# untitled.net
KiCad netlist of a schematic drawn in EAGLE
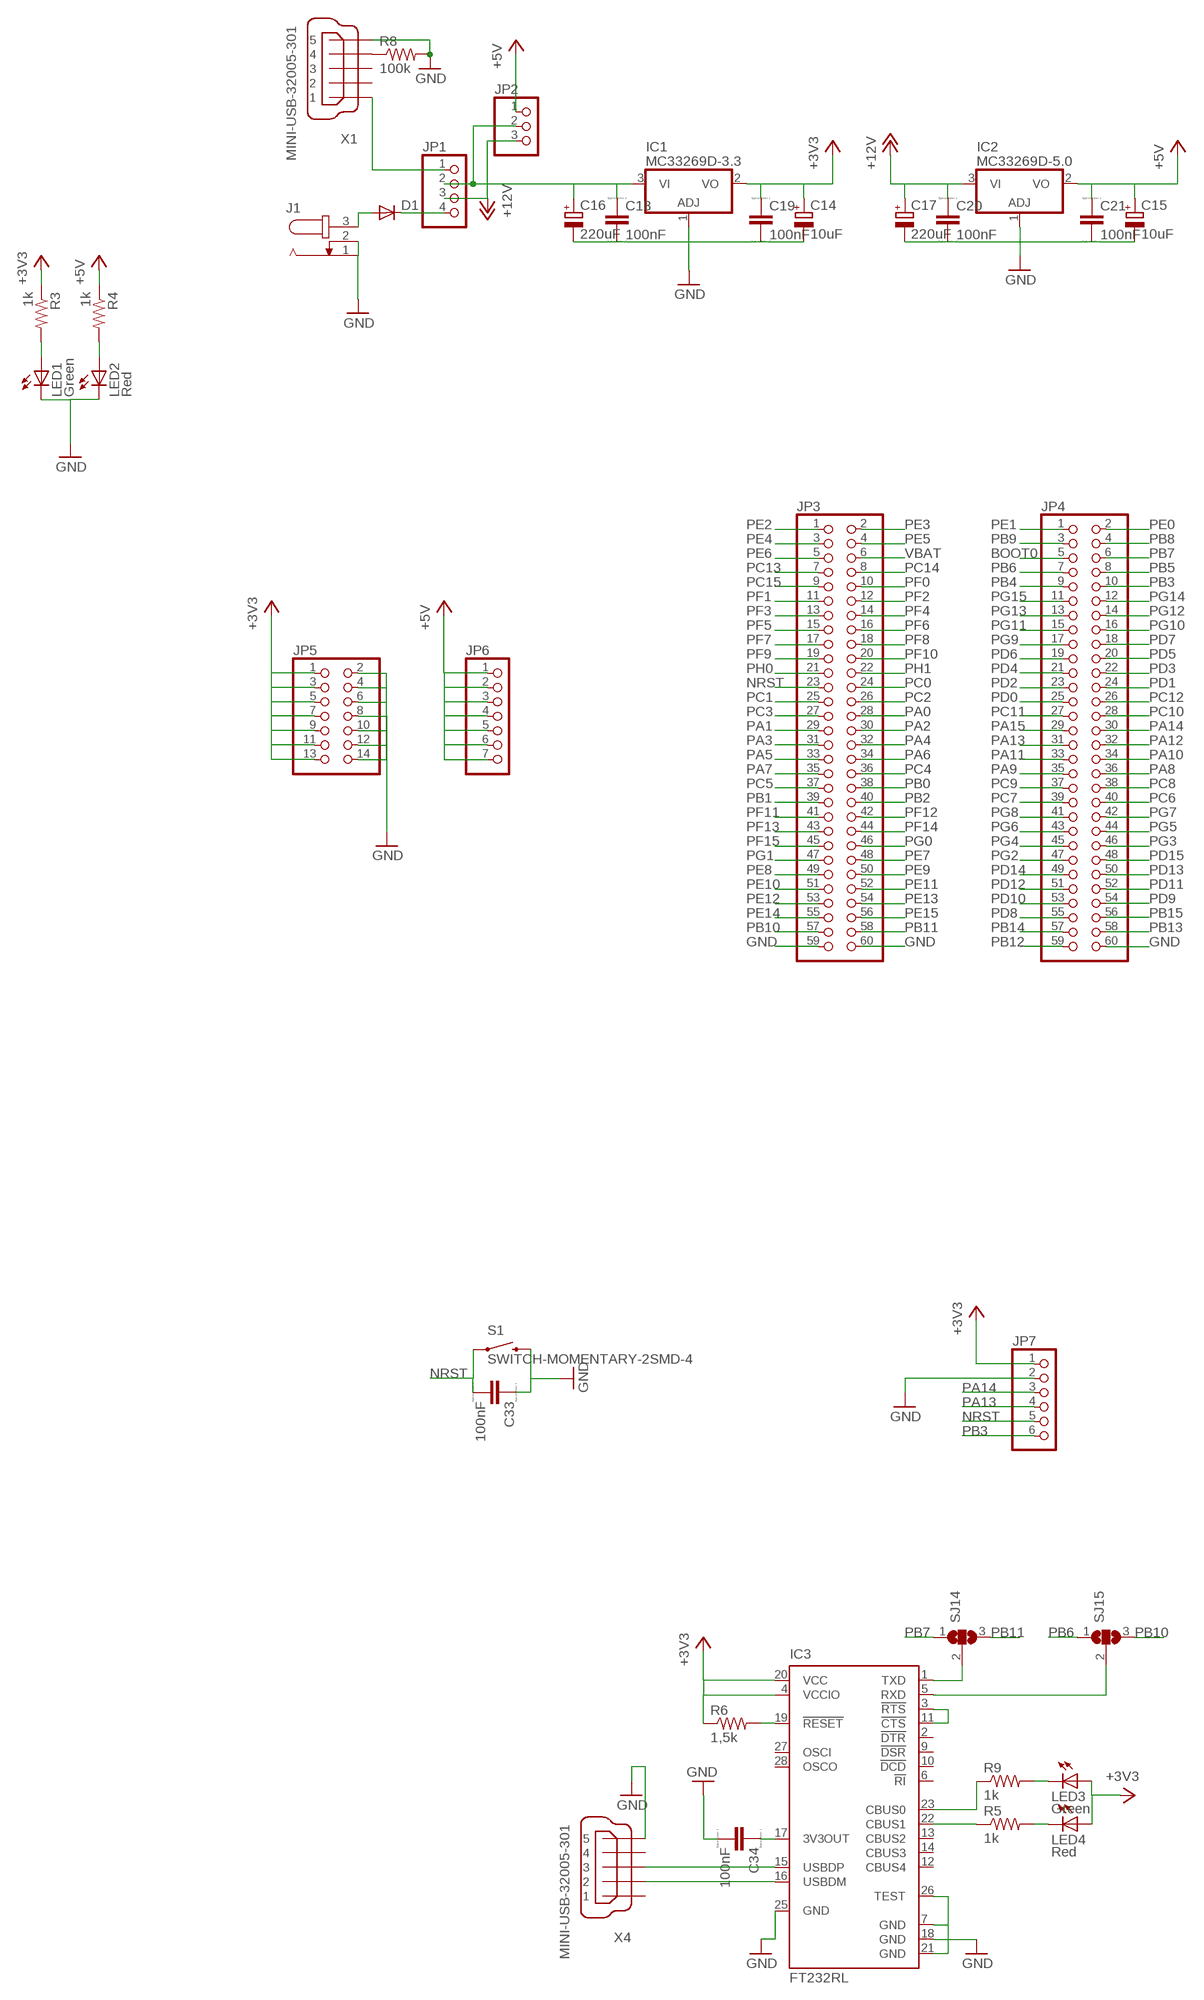
[diagram p0: schematic, sheet 1, part 1 of 2]
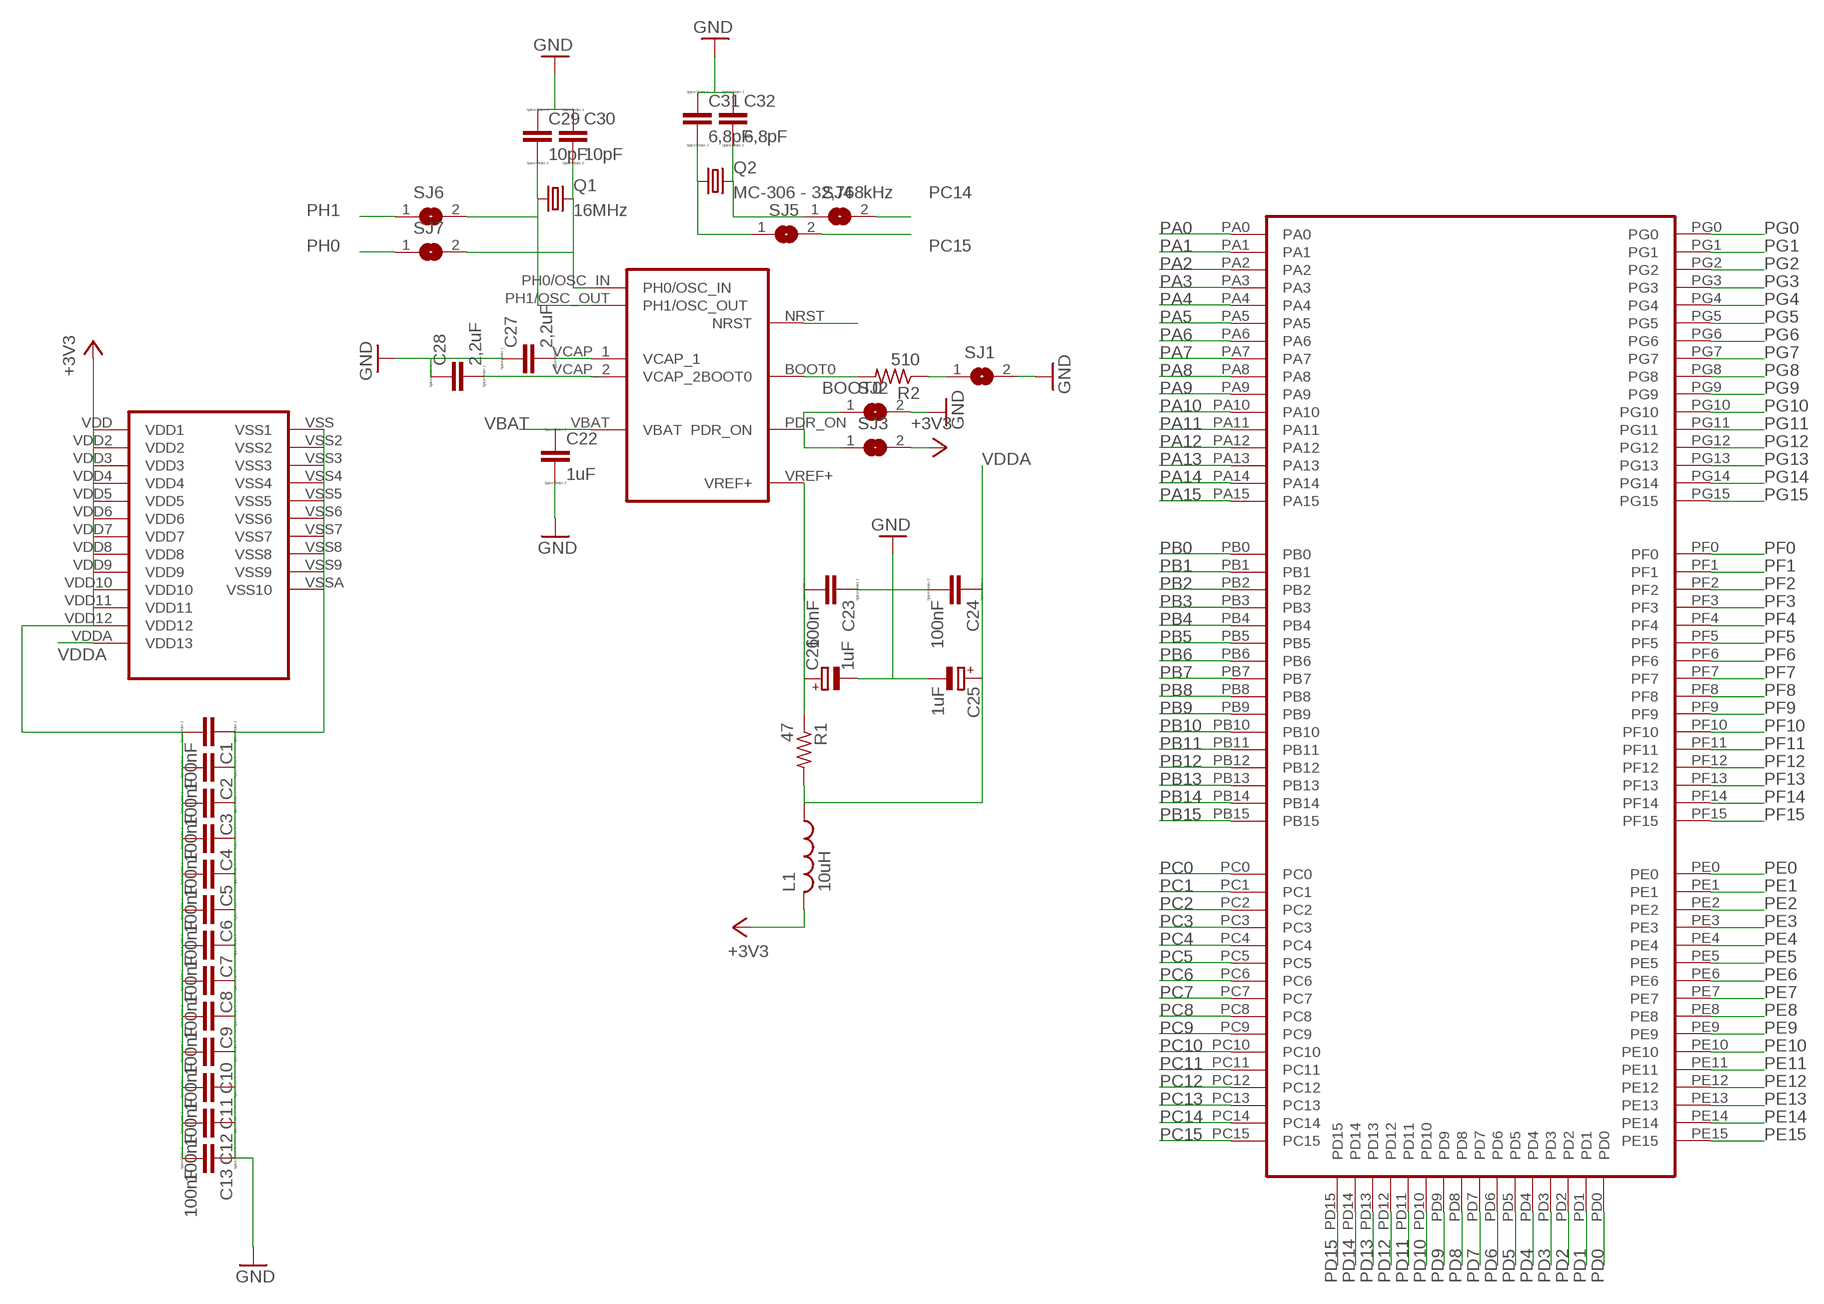
[diagram p1: schematic, sheet 1, part 2 of 2]

(export (version "E")
  (design (tool "Eeschema 10.0.6"))
  (components
    (comp (ref "C1")
      (value "100nF")
      (footprint "eagle-import:C2012")
      (libsource (lib "eagle-import") (part "CC2012"))
    )
    (comp (ref "C2")
      (value "100nF")
      (footprint "eagle-import:C2012")
      (libsource (lib "eagle-import") (part "CC2012"))
    )
    (comp (ref "C3")
      (value "100nF")
      (footprint "eagle-import:C2012")
      (libsource (lib "eagle-import") (part "CC2012"))
    )
    (comp (ref "C4")
      (value "100nF")
      (footprint "eagle-import:C2012")
      (libsource (lib "eagle-import") (part "CC2012"))
    )
    (comp (ref "C5")
      (value "100nF")
      (footprint "eagle-import:C2012")
      (libsource (lib "eagle-import") (part "CC2012"))
    )
    (comp (ref "C6")
      (value "100nF")
      (footprint "eagle-import:C2012")
      (libsource (lib "eagle-import") (part "CC2012"))
    )
    (comp (ref "C7")
      (value "100nF")
      (footprint "eagle-import:C2012")
      (libsource (lib "eagle-import") (part "CC2012"))
    )
    (comp (ref "C8")
      (value "100nF")
      (footprint "eagle-import:C2012")
      (libsource (lib "eagle-import") (part "CC2012"))
    )
    (comp (ref "C9")
      (value "100nF")
      (footprint "eagle-import:C2012")
      (libsource (lib "eagle-import") (part "CC2012"))
    )
    (comp (ref "C10")
      (value "100nF")
      (footprint "eagle-import:C2012")
      (libsource (lib "eagle-import") (part "CC2012"))
    )
    (comp (ref "C11")
      (value "100nF")
      (footprint "eagle-import:C2012")
      (libsource (lib "eagle-import") (part "CC2012"))
    )
    (comp (ref "C12")
      (value "100nF")
      (footprint "eagle-import:C2012")
      (libsource (lib "eagle-import") (part "CC2012"))
    )
    (comp (ref "C13")
      (value "100nF")
      (footprint "eagle-import:C2012")
      (libsource (lib "eagle-import") (part "CC2012"))
    )
    (comp (ref "C14")
      (value "10uF")
      (footprint "eagle-import:SMC_C")
      (libsource (lib "eagle-import") (part "resistor_CPOL-EUSMCC"))
    )
    (comp (ref "C15")
      (value "10uF")
      (footprint "eagle-import:SMC_C")
      (libsource (lib "eagle-import") (part "resistor_CPOL-EUSMCC"))
    )
    (comp (ref "C16")
      (value "220uF")
      (footprint "eagle-import:PANASONIC_D")
      (libsource (lib "eagle-import") (part "resistor_CPOL-EUD"))
    )
    (comp (ref "C17")
      (value "220uF")
      (footprint "eagle-import:PANASONIC_D")
      (libsource (lib "eagle-import") (part "resistor_CPOL-EUD"))
    )
    (comp (ref "C18")
      (value "100nF")
      (footprint "eagle-import:C2012")
      (libsource (lib "eagle-import") (part "CC2012"))
    )
    (comp (ref "C19")
      (value "100nF")
      (footprint "eagle-import:C2012")
      (libsource (lib "eagle-import") (part "CC2012"))
    )
    (comp (ref "C20")
      (value "100nF")
      (footprint "eagle-import:C2012")
      (libsource (lib "eagle-import") (part "CC2012"))
    )
    (comp (ref "C21")
      (value "100nF")
      (footprint "eagle-import:C2012")
      (libsource (lib "eagle-import") (part "CC2012"))
    )
    (comp (ref "C22")
      (value "1uF")
      (footprint "eagle-import:C2012")
      (libsource (lib "eagle-import") (part "CC2012"))
    )
    (comp (ref "C23")
      (value "100nF")
      (footprint "eagle-import:C2012")
      (libsource (lib "eagle-import") (part "CC2012"))
    )
    (comp (ref "C24")
      (value "100nF")
      (footprint "eagle-import:C2012")
      (libsource (lib "eagle-import") (part "CC2012"))
    )
    (comp (ref "C25")
      (value "1uF")
      (footprint "eagle-import:SMC_A")
      (libsource (lib "eagle-import") (part "CPOL-EUSMCA"))
    )
    (comp (ref "C26")
      (value "1uF")
      (footprint "eagle-import:SMC_A")
      (libsource (lib "eagle-import") (part "CPOL-EUSMCA"))
    )
    (comp (ref "C27")
      (value "2,2uF")
      (footprint "eagle-import:C2012")
      (libsource (lib "eagle-import") (part "CC2012"))
    )
    (comp (ref "C28")
      (value "2,2uF")
      (footprint "eagle-import:C2012")
      (libsource (lib "eagle-import") (part "CC2012"))
    )
    (comp (ref "C29")
      (value "10pF")
      (footprint "eagle-import:C2012")
      (libsource (lib "eagle-import") (part "CC2012"))
    )
    (comp (ref "C30")
      (value "10pF")
      (footprint "eagle-import:C2012")
      (libsource (lib "eagle-import") (part "CC2012"))
    )
    (comp (ref "C31")
      (value "6,8pF")
      (footprint "eagle-import:C2012")
      (libsource (lib "eagle-import") (part "CC2012"))
    )
    (comp (ref "C32")
      (value "6,8pF")
      (footprint "eagle-import:C2012")
      (libsource (lib "eagle-import") (part "CC2012"))
    )
    (comp (ref "C33")
      (value "100nF")
      (footprint "eagle-import:C2012")
      (libsource (lib "eagle-import") (part "CC2012"))
    )
    (comp (ref "C34")
      (value "100nF")
      (footprint "eagle-import:C2012")
      (libsource (lib "eagle-import") (part "CC2012"))
    )
    (comp (ref "D1")
      (value "DIODE-SOD323-W")
      (footprint "eagle-import:SOD323-W")
      (libsource (lib "eagle-import") (part "DIODE-SOD323-W"))
    )
    (comp (ref "IC1")
      (value "MC33269D-3.3")
      (footprint "eagle-import:DPACK")
      (libsource (lib "eagle-import") (part "MC33269?D-3.3"))
    )
    (comp (ref "IC2")
      (value "MC33269D-5.0")
      (footprint "eagle-import:DPACK")
      (libsource (lib "eagle-import") (part "MC33269?D-5.0"))
    )
    (comp (ref "IC3")
      (value "FT232RL")
      (footprint "eagle-import:SSOP28")
      (libsource (lib "eagle-import") (part "FT232RL"))
    )
    (comp (ref "J1")
      (value "JACK-PLUG1")
      (footprint "eagle-import:SPC4078")
      (libsource (lib "eagle-import") (part "JACK-PLUG1"))
    )
    (comp (ref "JP1")
      (value "PINHD-1X4")
      (footprint "eagle-import:1X04")
      (libsource (lib "eagle-import") (part "PINHD-1X4"))
    )
    (comp (ref "JP2")
      (value "PINHD-1X3")
      (footprint "eagle-import:1X03")
      (libsource (lib "eagle-import") (part "PINHD-1X3"))
    )
    (comp (ref "JP3")
      (value "PINHD-2X30")
      (footprint "eagle-import:2X30")
      (libsource (lib "eagle-import") (part "PINHD-2X30"))
    )
    (comp (ref "JP4")
      (value "PINHD-2X30")
      (footprint "eagle-import:2X30")
      (libsource (lib "eagle-import") (part "PINHD-2X30"))
    )
    (comp (ref "JP5")
      (value "PINHD-2X7")
      (footprint "eagle-import:2X07")
      (libsource (lib "eagle-import") (part "PINHD-2X7"))
    )
    (comp (ref "JP6")
      (value "PINHD-1X7")
      (footprint "eagle-import:1X07")
      (libsource (lib "eagle-import") (part "PINHD-1X7"))
    )
    (comp (ref "JP7")
      (value "PINHD-1X6")
      (footprint "eagle-import:1X06")
      (libsource (lib "eagle-import") (part "PINHD-1X6"))
    )
    (comp (ref "L1")
      (value "10uH")
      (footprint "eagle-import:L2012C")
      (libsource (lib "eagle-import") (part "L-USL2012C"))
    )
    (comp (ref "LED1")
      (value "Green")
      (footprint "eagle-import:CHIP-LED0805")
      (libsource (lib "eagle-import") (part "LEDCHIP-LED0805"))
    )
    (comp (ref "LED2")
      (value "Red")
      (footprint "eagle-import:CHIP-LED0805")
      (libsource (lib "eagle-import") (part "LEDCHIP-LED0805"))
    )
    (comp (ref "LED3")
      (value "Green")
      (footprint "eagle-import:CHIP-LED0805")
      (libsource (lib "eagle-import") (part "LEDCHIP-LED0805"))
    )
    (comp (ref "LED4")
      (value "Red")
      (footprint "eagle-import:CHIP-LED0805")
      (libsource (lib "eagle-import") (part "LEDCHIP-LED0805"))
    )
    (comp (ref "Q1")
      (value "16MHz")
      (footprint "eagle-import:HC49UP")
      (libsource (lib "eagle-import") (part "CRYSTALHC49UP"))
    )
    (comp (ref "Q2")
      (value "MC-306 - 32,768kHz")
      (footprint "eagle-import:MC-306")
      (fields (field (name "MPN") "MC-306 60.0KHZ  100PPM ,12.5PF"))
      (libsource (lib "eagle-import") (part "MC-306"))
    )
    (comp (ref "R1")
      (value "47")
      (footprint "eagle-import:R0805")
      (libsource (lib "eagle-import") (part "R-US_R0805"))
    )
    (comp (ref "R2")
      (value "510")
      (footprint "eagle-import:R0805")
      (libsource (lib "eagle-import") (part "R-US_R0805"))
    )
    (comp (ref "R3")
      (value "1k")
      (footprint "eagle-import:R0805")
      (libsource (lib "eagle-import") (part "R-US_R0805"))
    )
    (comp (ref "R4")
      (value "1k")
      (footprint "eagle-import:R0805")
      (libsource (lib "eagle-import") (part "R-US_R0805"))
    )
    (comp (ref "R5")
      (value "1k")
      (footprint "eagle-import:R0805")
      (libsource (lib "eagle-import") (part "R-US_R0805"))
    )
    (comp (ref "R6")
      (value "1,5k")
      (footprint "eagle-import:R0805")
      (libsource (lib "eagle-import") (part "R-US_R0805"))
    )
    (comp (ref "R8")
      (value "100k")
      (footprint "eagle-import:R0805")
      (libsource (lib "eagle-import") (part "R-US_R0805"))
    )
    (comp (ref "R9")
      (value "1k")
      (footprint "eagle-import:R0805")
      (libsource (lib "eagle-import") (part "R-US_R0805"))
    )
    (comp (ref "S1")
      (value "SWITCH-MOMENTARY-2SMD-4")
      (footprint "eagle-import:TACTILE_SWITCH_TALL")
      (libsource (lib "eagle-import") (part "SWITCH-MOMENTARY-2SMD-4"))
    )
    (comp (ref "SJ1") (value "SJ") (footprint "eagle-import:SJ") (libsource (lib "eagle-import") (part "SJ")))
    (comp (ref "SJ2") (value "SJ") (footprint "eagle-import:SJ") (libsource (lib "eagle-import") (part "SJ")))
    (comp (ref "SJ3") (value "SJ") (footprint "eagle-import:SJ") (libsource (lib "eagle-import") (part "SJ")))
    (comp (ref "SJ4") (value "SJ") (footprint "eagle-import:SJ") (libsource (lib "eagle-import") (part "SJ")))
    (comp (ref "SJ5") (value "SJ") (footprint "eagle-import:SJ") (libsource (lib "eagle-import") (part "SJ")))
    (comp (ref "SJ6") (value "SJ") (footprint "eagle-import:SJ") (libsource (lib "eagle-import") (part "SJ")))
    (comp (ref "SJ7") (value "SJ") (footprint "eagle-import:SJ") (libsource (lib "eagle-import") (part "SJ")))
    (comp (ref "SJ14")
      (value "SJ2W")
      (footprint "eagle-import:SJ_2")
      (libsource (lib "eagle-import") (part "SJ2W"))
    )
    (comp (ref "SJ15")
      (value "SJ2W")
      (footprint "eagle-import:SJ_2")
      (libsource (lib "eagle-import") (part "SJ2W"))
    )
    (comp (ref "U$1")
      (value "STM32F407LQFP144")
      (footprint "eagle-import:LQFP144_20")
      (libsource (lib "eagle-import") (part "STM32F407LQFP144"))
    )
    (comp (ref "X1")
      (value "MINI-USB-32005-301")
      (footprint "eagle-import:32005-301")
      (libsource (lib "eagle-import") (part "MINI-USB-32005-301"))
    )
    (comp (ref "X4")
      (value "MINI-USB-32005-301")
      (footprint "eagle-import:32005-301")
      (libsource (lib "eagle-import") (part "MINI-USB-32005-301"))
    )
  )
  (nets
    (net (code "1") (name "+3V3") (class "Default")
      (node (ref "C1") (pin "2") (pinfunction "2_2") (pintype "passive"))
      (node (ref "C10") (pin "2") (pinfunction "2_2") (pintype "passive"))
      (node (ref "C11") (pin "2") (pinfunction "2_2") (pintype "passive"))
      (node (ref "C12") (pin "2") (pinfunction "2_2") (pintype "passive"))
      (node (ref "C13") (pin "2") (pinfunction "2_2") (pintype "passive"))
      (node (ref "C14") (pin "+") (pinfunction "+_+") (pintype "passive"))
      (node (ref "C19") (pin "1") (pinfunction "1_1") (pintype "passive"))
      (node (ref "C2") (pin "2") (pinfunction "2_2") (pintype "passive"))
      (node (ref "C3") (pin "2") (pinfunction "2_2") (pintype "passive"))
      (node (ref "C4") (pin "2") (pinfunction "2_2") (pintype "passive"))
      (node (ref "C5") (pin "2") (pinfunction "2_2") (pintype "passive"))
      (node (ref "C6") (pin "2") (pinfunction "2_2") (pintype "passive"))
      (node (ref "C7") (pin "2") (pinfunction "2_2") (pintype "passive"))
      (node (ref "C8") (pin "2") (pinfunction "2_2") (pintype "passive"))
      (node (ref "C9") (pin "2") (pinfunction "2_2") (pintype "passive"))
      (node (ref "IC1") (pin "2") (pinfunction "VO_2") (pintype "passive"))
      (node (ref "IC3") (pin "20") (pinfunction "VCC_20") (pintype "power_in"))
      (node (ref "IC3") (pin "4") (pinfunction "VCCIO_4") (pintype "power_in"))
      (node (ref "JP5") (pin "1") (pinfunction "1_1") (pintype "passive"))
      (node (ref "JP5") (pin "11") (pinfunction "11_11") (pintype "passive"))
      (node (ref "JP5") (pin "13") (pinfunction "13_13") (pintype "passive"))
      (node (ref "JP5") (pin "3") (pinfunction "3_3") (pintype "passive"))
      (node (ref "JP5") (pin "5") (pinfunction "5_5") (pintype "passive"))
      (node (ref "JP5") (pin "7") (pinfunction "7_7") (pintype "passive"))
      (node (ref "JP5") (pin "9") (pinfunction "9_9") (pintype "passive"))
      (node (ref "JP7") (pin "1") (pinfunction "1_1") (pintype "passive"))
      (node (ref "L1") (pin "2") (pinfunction "2_2") (pintype "passive"))
      (node (ref "LED3") (pin "A") (pinfunction "A_A") (pintype "passive"))
      (node (ref "LED4") (pin "A") (pinfunction "A_A") (pintype "passive"))
      (node (ref "R3") (pin "1") (pinfunction "1_1") (pintype "passive"))
      (node (ref "R6") (pin "1") (pinfunction "1_1") (pintype "passive"))
      (node (ref "SJ3") (pin "2") (pinfunction "2_2") (pintype "passive"))
      (node (ref "U$1") (pin "VDD") (pinfunction "VDD1_VDD") (pintype "bidirectional"))
      (node (ref "U$1") (pin "VDD10") (pinfunction "VDD10_VDD10") (pintype "bidirectional"))
      (node (ref "U$1") (pin "VDD11") (pinfunction "VDD11_VDD11") (pintype "bidirectional"))
      (node (ref "U$1") (pin "VDD12") (pinfunction "VDD12_VDD12") (pintype "bidirectional"))
      (node (ref "U$1") (pin "VDD2") (pinfunction "VDD2_VDD2") (pintype "bidirectional"))
      (node (ref "U$1") (pin "VDD3") (pinfunction "VDD3_VDD3") (pintype "bidirectional"))
      (node (ref "U$1") (pin "VDD4") (pinfunction "VDD4_VDD4") (pintype "bidirectional"))
      (node (ref "U$1") (pin "VDD5") (pinfunction "VDD5_VDD5") (pintype "bidirectional"))
      (node (ref "U$1") (pin "VDD6") (pinfunction "VDD6_VDD6") (pintype "bidirectional"))
      (node (ref "U$1") (pin "VDD7") (pinfunction "VDD7_VDD7") (pintype "bidirectional"))
      (node (ref "U$1") (pin "VDD8") (pinfunction "VDD8_VDD8") (pintype "bidirectional"))
      (node (ref "U$1") (pin "VDD9") (pinfunction "VDD9_VDD9") (pintype "bidirectional"))
    )
    (net (code "2") (name "+5V") (class "Default")
      (node (ref "C15") (pin "+") (pinfunction "+_+") (pintype "passive"))
      (node (ref "C21") (pin "1") (pinfunction "1_1") (pintype "passive"))
      (node (ref "IC2") (pin "2") (pinfunction "VO_2") (pintype "passive"))
      (node (ref "JP2") (pin "1") (pinfunction "1_1") (pintype "passive"))
      (node (ref "JP6") (pin "1") (pinfunction "1_1") (pintype "passive"))
      (node (ref "JP6") (pin "2") (pinfunction "2_2") (pintype "passive"))
      (node (ref "JP6") (pin "3") (pinfunction "3_3") (pintype "passive"))
      (node (ref "JP6") (pin "4") (pinfunction "4_4") (pintype "passive"))
      (node (ref "JP6") (pin "5") (pinfunction "5_5") (pintype "passive"))
      (node (ref "JP6") (pin "6") (pinfunction "6_6") (pintype "passive"))
      (node (ref "JP6") (pin "7") (pinfunction "7_7") (pintype "passive"))
      (node (ref "R4") (pin "1") (pinfunction "1_1") (pintype "passive"))
    )
    (net (code "3") (name "+12V") (class "Default")
      (node (ref "C17") (pin "+") (pinfunction "+_+") (pintype "passive"))
      (node (ref "C20") (pin "1") (pinfunction "1_1") (pintype "passive"))
      (node (ref "IC2") (pin "3") (pinfunction "VI_3") (pintype "input"))
      (node (ref "JP1") (pin "3") (pinfunction "3_3") (pintype "passive"))
      (node (ref "JP2") (pin "3") (pinfunction "3_3") (pintype "passive"))
    )
    (net (code "4") (name "/BOOT0") (class "Default")
      (node (ref "JP4") (pin "5") (pinfunction "5_5") (pintype "passive"))
      (node (ref "R2") (pin "2") (pinfunction "2_2") (pintype "passive"))
      (node (ref "U$1") (pin "BOOT0") (pinfunction "BOOT0_BOOT0") (pintype "bidirectional"))
    )
    (net (code "5") (name "/NRST") (class "Default")
      (node (ref "C33") (pin "2") (pinfunction "2_2") (pintype "passive"))
      (node (ref "JP3") (pin "23") (pinfunction "23_23") (pintype "passive"))
      (node (ref "JP7") (pin "5") (pinfunction "5_5") (pintype "passive"))
      (node (ref "S1") (pin "A2") (pinfunction "1_A2") (pintype "passive"))
      (node (ref "U$1") (pin "NRST") (pinfunction "NRST_NRST") (pintype "bidirectional"))
    )
    (net (code "6") (name "/PA0") (class "Default")
      (node (ref "JP3") (pin "28") (pinfunction "28_28") (pintype "passive"))
      (node (ref "U$1") (pin "PA0") (pinfunction "PA0_PA0") (pintype "bidirectional"))
    )
    (net (code "7") (name "/PA1") (class "Default")
      (node (ref "JP3") (pin "29") (pinfunction "29_29") (pintype "passive"))
      (node (ref "U$1") (pin "PA1") (pinfunction "PA1_PA1") (pintype "bidirectional"))
    )
    (net (code "8") (name "/PA2") (class "Default")
      (node (ref "JP3") (pin "30") (pinfunction "30_30") (pintype "passive"))
      (node (ref "U$1") (pin "PA2") (pinfunction "PA2_PA2") (pintype "bidirectional"))
    )
    (net (code "9") (name "/PA3") (class "Default")
      (node (ref "JP3") (pin "31") (pinfunction "31_31") (pintype "passive"))
      (node (ref "U$1") (pin "PA3") (pinfunction "PA3_PA3") (pintype "bidirectional"))
    )
    (net (code "10") (name "/PA4") (class "Default")
      (node (ref "JP3") (pin "32") (pinfunction "32_32") (pintype "passive"))
      (node (ref "U$1") (pin "PA4") (pinfunction "PA4_PA4") (pintype "bidirectional"))
    )
    (net (code "11") (name "/PA5") (class "Default")
      (node (ref "JP3") (pin "33") (pinfunction "33_33") (pintype "passive"))
      (node (ref "U$1") (pin "PA5") (pinfunction "PA5_PA5") (pintype "bidirectional"))
    )
    (net (code "12") (name "/PA6") (class "Default")
      (node (ref "JP3") (pin "34") (pinfunction "34_34") (pintype "passive"))
      (node (ref "U$1") (pin "PA6") (pinfunction "PA6_PA6") (pintype "bidirectional"))
    )
    (net (code "13") (name "/PA7") (class "Default")
      (node (ref "JP3") (pin "35") (pinfunction "35_35") (pintype "passive"))
      (node (ref "U$1") (pin "PA7") (pinfunction "PA7_PA7") (pintype "bidirectional"))
    )
    (net (code "14") (name "/PA8") (class "Default")
      (node (ref "JP4") (pin "36") (pinfunction "36_36") (pintype "passive"))
      (node (ref "U$1") (pin "PA8") (pinfunction "PA8_PA8") (pintype "bidirectional"))
    )
    (net (code "15") (name "/PA9") (class "Default")
      (node (ref "JP4") (pin "35") (pinfunction "35_35") (pintype "passive"))
      (node (ref "U$1") (pin "PA9") (pinfunction "PA9_PA9") (pintype "bidirectional"))
    )
    (net (code "16") (name "/PA10") (class "Default")
      (node (ref "JP4") (pin "34") (pinfunction "34_34") (pintype "passive"))
      (node (ref "U$1") (pin "PA10") (pinfunction "PA10_PA10") (pintype "bidirectional"))
    )
    (net (code "17") (name "/PA11") (class "Default")
      (node (ref "JP4") (pin "33") (pinfunction "33_33") (pintype "passive"))
      (node (ref "U$1") (pin "PA11") (pinfunction "PA11_PA11") (pintype "bidirectional"))
    )
    (net (code "18") (name "/PA12") (class "Default")
      (node (ref "JP4") (pin "32") (pinfunction "32_32") (pintype "passive"))
      (node (ref "U$1") (pin "PA12") (pinfunction "PA12_PA12") (pintype "bidirectional"))
    )
    (net (code "19") (name "/PA13") (class "Default")
      (node (ref "JP4") (pin "31") (pinfunction "31_31") (pintype "passive"))
      (node (ref "JP7") (pin "4") (pinfunction "4_4") (pintype "passive"))
      (node (ref "U$1") (pin "PA13") (pinfunction "PA13_PA13") (pintype "bidirectional"))
    )
    (net (code "20") (name "/PA14") (class "Default")
      (node (ref "JP4") (pin "30") (pinfunction "30_30") (pintype "passive"))
      (node (ref "JP7") (pin "3") (pinfunction "3_3") (pintype "passive"))
      (node (ref "U$1") (pin "PA14") (pinfunction "PA14_PA14") (pintype "bidirectional"))
    )
    (net (code "21") (name "/PA15") (class "Default")
      (node (ref "JP4") (pin "29") (pinfunction "29_29") (pintype "passive"))
      (node (ref "U$1") (pin "PA15") (pinfunction "PA15_PA15") (pintype "bidirectional"))
    )
    (net (code "22") (name "/PB0") (class "Default")
      (node (ref "JP3") (pin "38") (pinfunction "38_38") (pintype "passive"))
      (node (ref "U$1") (pin "PB0") (pinfunction "PB0_PB0") (pintype "bidirectional"))
    )
    (net (code "23") (name "/PB1") (class "Default")
      (node (ref "JP3") (pin "39") (pinfunction "39_39") (pintype "passive"))
      (node (ref "U$1") (pin "PB1") (pinfunction "PB1_PB1") (pintype "bidirectional"))
    )
    (net (code "24") (name "/PB2") (class "Default")
      (node (ref "JP3") (pin "40") (pinfunction "40_40") (pintype "passive"))
      (node (ref "U$1") (pin "PB2") (pinfunction "PB2_PB2") (pintype "bidirectional"))
    )
    (net (code "25") (name "/PB3") (class "Default")
      (node (ref "JP4") (pin "10") (pinfunction "10_10") (pintype "passive"))
      (node (ref "JP7") (pin "6") (pinfunction "6_6") (pintype "passive"))
      (node (ref "U$1") (pin "PB3") (pinfunction "PB3_PB3") (pintype "bidirectional"))
    )
    (net (code "26") (name "/PB4") (class "Default")
      (node (ref "JP4") (pin "9") (pinfunction "9_9") (pintype "passive"))
      (node (ref "U$1") (pin "PB4") (pinfunction "PB4_PB4") (pintype "bidirectional"))
    )
    (net (code "27") (name "/PB5") (class "Default")
      (node (ref "JP4") (pin "8") (pinfunction "8_8") (pintype "passive"))
      (node (ref "U$1") (pin "PB5") (pinfunction "PB5_PB5") (pintype "bidirectional"))
    )
    (net (code "28") (name "/PB6") (class "Default")
      (node (ref "JP4") (pin "7") (pinfunction "7_7") (pintype "passive"))
      (node (ref "SJ15") (pin "1") (pinfunction "1_1") (pintype "passive"))
      (node (ref "U$1") (pin "PB6") (pinfunction "PB6_PB6") (pintype "bidirectional"))
    )
    (net (code "29") (name "/PB7") (class "Default")
      (node (ref "JP4") (pin "6") (pinfunction "6_6") (pintype "passive"))
      (node (ref "SJ14") (pin "1") (pinfunction "1_1") (pintype "passive"))
      (node (ref "U$1") (pin "PB7") (pinfunction "PB7_PB7") (pintype "bidirectional"))
    )
    (net (code "30") (name "/PB8") (class "Default")
      (node (ref "JP4") (pin "4") (pinfunction "4_4") (pintype "passive"))
      (node (ref "U$1") (pin "PB8") (pinfunction "PB8_PB8") (pintype "bidirectional"))
    )
    (net (code "31") (name "/PB9") (class "Default")
      (node (ref "JP4") (pin "3") (pinfunction "3_3") (pintype "passive"))
      (node (ref "U$1") (pin "PB9") (pinfunction "PB9_PB9") (pintype "bidirectional"))
    )
    (net (code "32") (name "/PB10") (class "Default")
      (node (ref "JP3") (pin "57") (pinfunction "57_57") (pintype "passive"))
      (node (ref "SJ15") (pin "3") (pinfunction "3_3") (pintype "passive"))
      (node (ref "U$1") (pin "PB10") (pinfunction "PB10_PB10") (pintype "bidirectional"))
    )
    (net (code "33") (name "/PB11") (class "Default")
      (node (ref "JP3") (pin "58") (pinfunction "58_58") (pintype "passive"))
      (node (ref "SJ14") (pin "3") (pinfunction "3_3") (pintype "passive"))
      (node (ref "U$1") (pin "PB11") (pinfunction "PB11_PB11") (pintype "bidirectional"))
    )
    (net (code "34") (name "/PB12") (class "Default")
      (node (ref "JP4") (pin "59") (pinfunction "59_59") (pintype "passive"))
      (node (ref "U$1") (pin "PB12") (pinfunction "PB12_PB12") (pintype "bidirectional"))
    )
    (net (code "35") (name "/PB13") (class "Default")
      (node (ref "JP4") (pin "58") (pinfunction "58_58") (pintype "passive"))
      (node (ref "U$1") (pin "PB13") (pinfunction "PB13_PB13") (pintype "bidirectional"))
    )
    (net (code "36") (name "/PB14") (class "Default")
      (node (ref "JP4") (pin "57") (pinfunction "57_57") (pintype "passive"))
      (node (ref "U$1") (pin "PB14") (pinfunction "PB14_PB14") (pintype "bidirectional"))
    )
    (net (code "37") (name "/PB15") (class "Default")
      (node (ref "JP4") (pin "56") (pinfunction "56_56") (pintype "passive"))
      (node (ref "U$1") (pin "PB15") (pinfunction "PB15_PB15") (pintype "bidirectional"))
    )
    (net (code "38") (name "/PC0") (class "Default")
      (node (ref "JP3") (pin "24") (pinfunction "24_24") (pintype "passive"))
      (node (ref "U$1") (pin "PC0") (pinfunction "PC0_PC0") (pintype "bidirectional"))
    )
    (net (code "39") (name "/PC1") (class "Default")
      (node (ref "JP3") (pin "25") (pinfunction "25_25") (pintype "passive"))
      (node (ref "U$1") (pin "PC1") (pinfunction "PC1_PC1") (pintype "bidirectional"))
    )
    (net (code "40") (name "/PC2") (class "Default")
      (node (ref "JP3") (pin "26") (pinfunction "26_26") (pintype "passive"))
      (node (ref "U$1") (pin "PC2") (pinfunction "PC2_PC2") (pintype "bidirectional"))
    )
    (net (code "41") (name "/PC3") (class "Default")
      (node (ref "JP3") (pin "27") (pinfunction "27_27") (pintype "passive"))
      (node (ref "U$1") (pin "PC3") (pinfunction "PC3_PC3") (pintype "bidirectional"))
    )
    (net (code "42") (name "/PC4") (class "Default")
      (node (ref "JP3") (pin "36") (pinfunction "36_36") (pintype "passive"))
      (node (ref "U$1") (pin "PC4") (pinfunction "PC4_PC4") (pintype "bidirectional"))
    )
    (net (code "43") (name "/PC5") (class "Default")
      (node (ref "JP3") (pin "37") (pinfunction "37_37") (pintype "passive"))
      (node (ref "U$1") (pin "PC5") (pinfunction "PC5_PC5") (pintype "bidirectional"))
    )
    (net (code "44") (name "/PC6") (class "Default")
      (node (ref "JP4") (pin "40") (pinfunction "40_40") (pintype "passive"))
      (node (ref "U$1") (pin "PC6") (pinfunction "PC6_PC6") (pintype "bidirectional"))
    )
    (net (code "45") (name "/PC7") (class "Default")
      (node (ref "JP4") (pin "39") (pinfunction "39_39") (pintype "passive"))
      (node (ref "U$1") (pin "PC7") (pinfunction "PC7_PC7") (pintype "bidirectional"))
    )
    (net (code "46") (name "/PC8") (class "Default")
      (node (ref "JP4") (pin "38") (pinfunction "38_38") (pintype "passive"))
      (node (ref "U$1") (pin "PC8") (pinfunction "PC8_PC8") (pintype "bidirectional"))
    )
    (net (code "47") (name "/PC9") (class "Default")
      (node (ref "JP4") (pin "37") (pinfunction "37_37") (pintype "passive"))
      (node (ref "U$1") (pin "PC9") (pinfunction "PC9_PC9") (pintype "bidirectional"))
    )
    (net (code "48") (name "/PC10") (class "Default")
      (node (ref "JP4") (pin "28") (pinfunction "28_28") (pintype "passive"))
      (node (ref "U$1") (pin "PC10") (pinfunction "PC10_PC10") (pintype "bidirectional"))
    )
    (net (code "49") (name "/PC11") (class "Default")
      (node (ref "JP4") (pin "27") (pinfunction "27_27") (pintype "passive"))
      (node (ref "U$1") (pin "PC11") (pinfunction "PC11_PC11") (pintype "bidirectional"))
    )
    (net (code "50") (name "/PC12") (class "Default")
      (node (ref "JP4") (pin "26") (pinfunction "26_26") (pintype "passive"))
      (node (ref "U$1") (pin "PC12") (pinfunction "PC12_PC12") (pintype "bidirectional"))
    )
    (net (code "51") (name "/PC13") (class "Default")
      (node (ref "JP3") (pin "7") (pinfunction "7_7") (pintype "passive"))
      (node (ref "U$1") (pin "PC13") (pinfunction "PC13_PC13") (pintype "bidirectional"))
    )
    (net (code "52") (name "/PC14") (class "Default")
      (node (ref "JP3") (pin "8") (pinfunction "8_8") (pintype "passive"))
      (node (ref "SJ4") (pin "2") (pinfunction "2_2") (pintype "passive"))
      (node (ref "U$1") (pin "PC14") (pinfunction "PC14_PC14") (pintype "bidirectional"))
    )
    (net (code "53") (name "/PC15") (class "Default")
      (node (ref "JP3") (pin "9") (pinfunction "9_9") (pintype "passive"))
      (node (ref "SJ5") (pin "2") (pinfunction "2_2") (pintype "passive"))
      (node (ref "U$1") (pin "PC15") (pinfunction "PC15_PC15") (pintype "bidirectional"))
    )
    (net (code "54") (name "/PD0") (class "Default")
      (node (ref "JP4") (pin "25") (pinfunction "25_25") (pintype "passive"))
      (node (ref "U$1") (pin "PD0") (pinfunction "PD0_PD0") (pintype "bidirectional"))
    )
    (net (code "55") (name "/PD1") (class "Default")
      (node (ref "JP4") (pin "24") (pinfunction "24_24") (pintype "passive"))
      (node (ref "U$1") (pin "PD1") (pinfunction "PD1_PD1") (pintype "bidirectional"))
    )
    (net (code "56") (name "/PD2") (class "Default")
      (node (ref "JP4") (pin "23") (pinfunction "23_23") (pintype "passive"))
      (node (ref "U$1") (pin "PD2") (pinfunction "PD2_PD2") (pintype "bidirectional"))
    )
    (net (code "57") (name "/PD3") (class "Default")
      (node (ref "JP4") (pin "22") (pinfunction "22_22") (pintype "passive"))
      (node (ref "U$1") (pin "PD3") (pinfunction "PD3_PD3") (pintype "bidirectional"))
    )
    (net (code "58") (name "/PD4") (class "Default")
      (node (ref "JP4") (pin "21") (pinfunction "21_21") (pintype "passive"))
      (node (ref "U$1") (pin "PD4") (pinfunction "PD4_PD4") (pintype "bidirectional"))
    )
    (net (code "59") (name "/PD5") (class "Default")
      (node (ref "JP4") (pin "20") (pinfunction "20_20") (pintype "passive"))
      (node (ref "U$1") (pin "PD5") (pinfunction "PD5_PD5") (pintype "bidirectional"))
    )
    (net (code "60") (name "/PD6") (class "Default")
      (node (ref "JP4") (pin "19") (pinfunction "19_19") (pintype "passive"))
      (node (ref "U$1") (pin "PD6") (pinfunction "PD6_PD6") (pintype "bidirectional"))
    )
    (net (code "61") (name "/PD7") (class "Default")
      (node (ref "JP4") (pin "18") (pinfunction "18_18") (pintype "passive"))
      (node (ref "U$1") (pin "PD7") (pinfunction "PD7_PD7") (pintype "bidirectional"))
    )
    (net (code "62") (name "/PD8") (class "Default")
      (node (ref "JP4") (pin "55") (pinfunction "55_55") (pintype "passive"))
      (node (ref "U$1") (pin "PD8") (pinfunction "PD8_PD8") (pintype "bidirectional"))
    )
    (net (code "63") (name "/PD9") (class "Default")
      (node (ref "JP4") (pin "54") (pinfunction "54_54") (pintype "passive"))
      (node (ref "U$1") (pin "PD9") (pinfunction "PD9_PD9") (pintype "bidirectional"))
    )
    (net (code "64") (name "/PD10") (class "Default")
      (node (ref "JP4") (pin "53") (pinfunction "53_53") (pintype "passive"))
      (node (ref "U$1") (pin "PD10") (pinfunction "PD10_PD10") (pintype "bidirectional"))
    )
    (net (code "65") (name "/PD11") (class "Default")
      (node (ref "JP4") (pin "52") (pinfunction "52_52") (pintype "passive"))
      (node (ref "U$1") (pin "PD11") (pinfunction "PD11_PD11") (pintype "bidirectional"))
    )
    (net (code "66") (name "/PD12") (class "Default")
      (node (ref "JP4") (pin "51") (pinfunction "51_51") (pintype "passive"))
      (node (ref "U$1") (pin "PD12") (pinfunction "PD12_PD12") (pintype "bidirectional"))
    )
    (net (code "67") (name "/PD13") (class "Default")
      (node (ref "JP4") (pin "50") (pinfunction "50_50") (pintype "passive"))
      (node (ref "U$1") (pin "PD13") (pinfunction "PD13_PD13") (pintype "bidirectional"))
    )
    (net (code "68") (name "/PD14") (class "Default")
      (node (ref "JP4") (pin "49") (pinfunction "49_49") (pintype "passive"))
      (node (ref "U$1") (pin "PD14") (pinfunction "PD14_PD14") (pintype "bidirectional"))
    )
    (net (code "69") (name "/PD15") (class "Default")
      (node (ref "JP4") (pin "48") (pinfunction "48_48") (pintype "passive"))
      (node (ref "U$1") (pin "PD15") (pinfunction "PD15_PD15") (pintype "bidirectional"))
    )
    (net (code "70") (name "/PE0") (class "Default")
      (node (ref "JP4") (pin "2") (pinfunction "2_2") (pintype "passive"))
      (node (ref "U$1") (pin "PE0") (pinfunction "PE0_PE0") (pintype "bidirectional"))
    )
    (net (code "71") (name "/PE1") (class "Default")
      (node (ref "JP4") (pin "1") (pinfunction "1_1") (pintype "passive"))
      (node (ref "U$1") (pin "PE1") (pinfunction "PE1_PE1") (pintype "bidirectional"))
    )
    (net (code "72") (name "/PE2") (class "Default")
      (node (ref "JP3") (pin "1") (pinfunction "1_1") (pintype "passive"))
      (node (ref "U$1") (pin "PE2") (pinfunction "PE2_PE2") (pintype "bidirectional"))
    )
    (net (code "73") (name "/PE3") (class "Default")
      (node (ref "JP3") (pin "2") (pinfunction "2_2") (pintype "passive"))
      (node (ref "U$1") (pin "PE3") (pinfunction "PE3_PE3") (pintype "bidirectional"))
    )
    (net (code "74") (name "/PE4") (class "Default")
      (node (ref "JP3") (pin "3") (pinfunction "3_3") (pintype "passive"))
      (node (ref "U$1") (pin "PE4") (pinfunction "PE4_PE4") (pintype "bidirectional"))
    )
    (net (code "75") (name "/PE5") (class "Default")
      (node (ref "JP3") (pin "4") (pinfunction "4_4") (pintype "passive"))
      (node (ref "U$1") (pin "PE5") (pinfunction "PE5_PE5") (pintype "bidirectional"))
    )
    (net (code "76") (name "/PE6") (class "Default")
      (node (ref "JP3") (pin "5") (pinfunction "5_5") (pintype "passive"))
      (node (ref "U$1") (pin "PE6") (pinfunction "PE6_PE6") (pintype "bidirectional"))
    )
    (net (code "77") (name "/PE7") (class "Default")
      (node (ref "JP3") (pin "48") (pinfunction "48_48") (pintype "passive"))
      (node (ref "U$1") (pin "PE7") (pinfunction "PE7_PE7") (pintype "bidirectional"))
    )
    (net (code "78") (name "/PE8") (class "Default")
      (node (ref "JP3") (pin "49") (pinfunction "49_49") (pintype "passive"))
      (node (ref "U$1") (pin "PE8") (pinfunction "PE8_PE8") (pintype "bidirectional"))
    )
    (net (code "79") (name "/PE9") (class "Default")
      (node (ref "JP3") (pin "50") (pinfunction "50_50") (pintype "passive"))
      (node (ref "U$1") (pin "PE9") (pinfunction "PE9_PE9") (pintype "bidirectional"))
    )
    (net (code "80") (name "/PE10") (class "Default")
      (node (ref "JP3") (pin "51") (pinfunction "51_51") (pintype "passive"))
      (node (ref "U$1") (pin "PE10") (pinfunction "PE10_PE10") (pintype "bidirectional"))
    )
    (net (code "81") (name "/PE11") (class "Default")
      (node (ref "JP3") (pin "52") (pinfunction "52_52") (pintype "passive"))
      (node (ref "U$1") (pin "PE11") (pinfunction "PE11_PE11") (pintype "bidirectional"))
    )
    (net (code "82") (name "/PE12") (class "Default")
      (node (ref "JP3") (pin "53") (pinfunction "53_53") (pintype "passive"))
      (node (ref "U$1") (pin "PE12") (pinfunction "PE12_PE12") (pintype "bidirectional"))
    )
    (net (code "83") (name "/PE13") (class "Default")
      (node (ref "JP3") (pin "54") (pinfunction "54_54") (pintype "passive"))
      (node (ref "U$1") (pin "PE13") (pinfunction "PE13_PE13") (pintype "bidirectional"))
    )
    (net (code "84") (name "/PE14") (class "Default")
      (node (ref "JP3") (pin "55") (pinfunction "55_55") (pintype "passive"))
      (node (ref "U$1") (pin "PE14") (pinfunction "PE14_PE14") (pintype "bidirectional"))
    )
    (net (code "85") (name "/PE15") (class "Default")
      (node (ref "JP3") (pin "56") (pinfunction "56_56") (pintype "passive"))
      (node (ref "U$1") (pin "PE15") (pinfunction "PE15_PE15") (pintype "bidirectional"))
    )
    (net (code "86") (name "/PF0") (class "Default")
      (node (ref "JP3") (pin "10") (pinfunction "10_10") (pintype "passive"))
      (node (ref "U$1") (pin "PF0") (pinfunction "PF0_PF0") (pintype "bidirectional"))
    )
    (net (code "87") (name "/PF1") (class "Default")
      (node (ref "JP3") (pin "11") (pinfunction "11_11") (pintype "passive"))
      (node (ref "U$1") (pin "PF1") (pinfunction "PF1_PF1") (pintype "bidirectional"))
    )
    (net (code "88") (name "/PF2") (class "Default")
      (node (ref "JP3") (pin "12") (pinfunction "12_12") (pintype "passive"))
      (node (ref "U$1") (pin "PF2") (pinfunction "PF2_PF2") (pintype "bidirectional"))
    )
    (net (code "89") (name "/PF3") (class "Default")
      (node (ref "JP3") (pin "13") (pinfunction "13_13") (pintype "passive"))
      (node (ref "U$1") (pin "PF3") (pinfunction "PF3_PF3") (pintype "bidirectional"))
    )
    (net (code "90") (name "/PF4") (class "Default")
      (node (ref "JP3") (pin "14") (pinfunction "14_14") (pintype "passive"))
      (node (ref "U$1") (pin "PF4") (pinfunction "PF4_PF4") (pintype "bidirectional"))
    )
    (net (code "91") (name "/PF5") (class "Default")
      (node (ref "JP3") (pin "15") (pinfunction "15_15") (pintype "passive"))
      (node (ref "U$1") (pin "PF5") (pinfunction "PF5_PF5") (pintype "bidirectional"))
    )
    (net (code "92") (name "/PF6") (class "Default")
      (node (ref "JP3") (pin "16") (pinfunction "16_16") (pintype "passive"))
      (node (ref "U$1") (pin "PF6") (pinfunction "PF6_PF6") (pintype "bidirectional"))
    )
    (net (code "93") (name "/PF7") (class "Default")
      (node (ref "JP3") (pin "17") (pinfunction "17_17") (pintype "passive"))
      (node (ref "U$1") (pin "PF7") (pinfunction "PF7_PF7") (pintype "bidirectional"))
    )
    (net (code "94") (name "/PF8") (class "Default")
      (node (ref "JP3") (pin "18") (pinfunction "18_18") (pintype "passive"))
      (node (ref "U$1") (pin "PF8") (pinfunction "PF8_PF8") (pintype "bidirectional"))
    )
    (net (code "95") (name "/PF9") (class "Default")
      (node (ref "JP3") (pin "19") (pinfunction "19_19") (pintype "passive"))
      (node (ref "U$1") (pin "PF9") (pinfunction "PF9_PF9") (pintype "bidirectional"))
    )
    (net (code "96") (name "/PF10") (class "Default")
      (node (ref "JP3") (pin "20") (pinfunction "20_20") (pintype "passive"))
      (node (ref "U$1") (pin "PF10") (pinfunction "PF10_PF10") (pintype "bidirectional"))
    )
    (net (code "97") (name "/PF11") (class "Default")
      (node (ref "JP3") (pin "41") (pinfunction "41_41") (pintype "passive"))
      (node (ref "U$1") (pin "PF11") (pinfunction "PF11_PF11") (pintype "bidirectional"))
    )
    (net (code "98") (name "/PF12") (class "Default")
      (node (ref "JP3") (pin "42") (pinfunction "42_42") (pintype "passive"))
      (node (ref "U$1") (pin "PF12") (pinfunction "PF12_PF12") (pintype "bidirectional"))
    )
    (net (code "99") (name "/PF13") (class "Default")
      (node (ref "JP3") (pin "43") (pinfunction "43_43") (pintype "passive"))
      (node (ref "U$1") (pin "PF13") (pinfunction "PF13_PF13") (pintype "bidirectional"))
    )
    (net (code "100") (name "/PF14") (class "Default")
      (node (ref "JP3") (pin "44") (pinfunction "44_44") (pintype "passive"))
      (node (ref "U$1") (pin "PF14") (pinfunction "PF14_PF14") (pintype "bidirectional"))
    )
    (net (code "101") (name "/PF15") (class "Default")
      (node (ref "JP3") (pin "45") (pinfunction "45_45") (pintype "passive"))
      (node (ref "U$1") (pin "PF15") (pinfunction "PF15_PF15") (pintype "bidirectional"))
    )
    (net (code "102") (name "/PG0") (class "Default")
      (node (ref "JP3") (pin "46") (pinfunction "46_46") (pintype "passive"))
      (node (ref "U$1") (pin "PG0") (pinfunction "PG0_PG0") (pintype "bidirectional"))
    )
    (net (code "103") (name "/PG1") (class "Default")
      (node (ref "JP3") (pin "47") (pinfunction "47_47") (pintype "passive"))
      (node (ref "U$1") (pin "PG1") (pinfunction "PG1_PG1") (pintype "bidirectional"))
    )
    (net (code "104") (name "/PG2") (class "Default")
      (node (ref "JP4") (pin "47") (pinfunction "47_47") (pintype "passive"))
      (node (ref "U$1") (pin "PG2") (pinfunction "PG2_PG2") (pintype "bidirectional"))
    )
    (net (code "105") (name "/PG3") (class "Default")
      (node (ref "JP4") (pin "46") (pinfunction "46_46") (pintype "passive"))
      (node (ref "U$1") (pin "PG3") (pinfunction "PG3_PG3") (pintype "bidirectional"))
    )
    (net (code "106") (name "/PG4") (class "Default")
      (node (ref "JP4") (pin "45") (pinfunction "45_45") (pintype "passive"))
      (node (ref "U$1") (pin "PG4") (pinfunction "PG4_PG4") (pintype "bidirectional"))
    )
    (net (code "107") (name "/PG5") (class "Default")
      (node (ref "JP4") (pin "44") (pinfunction "44_44") (pintype "passive"))
      (node (ref "U$1") (pin "PG5") (pinfunction "PG5_PG5") (pintype "bidirectional"))
    )
    (net (code "108") (name "/PG6") (class "Default")
      (node (ref "JP4") (pin "43") (pinfunction "43_43") (pintype "passive"))
      (node (ref "U$1") (pin "PG6") (pinfunction "PG6_PG6") (pintype "bidirectional"))
    )
    (net (code "109") (name "/PG7") (class "Default")
      (node (ref "JP4") (pin "42") (pinfunction "42_42") (pintype "passive"))
      (node (ref "U$1") (pin "PG7") (pinfunction "PG7_PG7") (pintype "bidirectional"))
    )
    (net (code "110") (name "/PG8") (class "Default")
      (node (ref "JP4") (pin "41") (pinfunction "41_41") (pintype "passive"))
      (node (ref "U$1") (pin "PG8") (pinfunction "PG8_PG8") (pintype "bidirectional"))
    )
    (net (code "111") (name "/PG9") (class "Default")
      (node (ref "JP4") (pin "17") (pinfunction "17_17") (pintype "passive"))
      (node (ref "U$1") (pin "PG9") (pinfunction "PG9_PG9") (pintype "bidirectional"))
    )
    (net (code "112") (name "/PG10") (class "Default")
      (node (ref "JP4") (pin "16") (pinfunction "16_16") (pintype "passive"))
      (node (ref "U$1") (pin "PG10") (pinfunction "PG10_PG10") (pintype "bidirectional"))
    )
    (net (code "113") (name "/PG11") (class "Default")
      (node (ref "JP4") (pin "15") (pinfunction "15_15") (pintype "passive"))
      (node (ref "U$1") (pin "PG11") (pinfunction "PG11_PG11") (pintype "bidirectional"))
    )
    (net (code "114") (name "/PG12") (class "Default")
      (node (ref "JP4") (pin "14") (pinfunction "14_14") (pintype "passive"))
      (node (ref "U$1") (pin "PG12") (pinfunction "PG12_PG12") (pintype "bidirectional"))
    )
    (net (code "115") (name "/PG13") (class "Default")
      (node (ref "JP4") (pin "13") (pinfunction "13_13") (pintype "passive"))
      (node (ref "U$1") (pin "PG13") (pinfunction "PG13_PG13") (pintype "bidirectional"))
    )
    (net (code "116") (name "/PG14") (class "Default")
      (node (ref "JP4") (pin "12") (pinfunction "12_12") (pintype "passive"))
      (node (ref "U$1") (pin "PG14") (pinfunction "PG14_PG14") (pintype "bidirectional"))
    )
    (net (code "117") (name "/PG15") (class "Default")
      (node (ref "JP4") (pin "11") (pinfunction "11_11") (pintype "passive"))
      (node (ref "U$1") (pin "PG15") (pinfunction "PG15_PG15") (pintype "bidirectional"))
    )
    (net (code "118") (name "/PH0") (class "Default")
      (node (ref "JP3") (pin "21") (pinfunction "21_21") (pintype "passive"))
      (node (ref "SJ7") (pin "1") (pinfunction "1_1") (pintype "passive"))
    )
    (net (code "119") (name "/PH1") (class "Default")
      (node (ref "JP3") (pin "22") (pinfunction "22_22") (pintype "passive"))
      (node (ref "SJ6") (pin "1") (pinfunction "1_1") (pintype "passive"))
    )
    (net (code "120") (name "/VBAT") (class "Default")
      (node (ref "C22") (pin "1") (pinfunction "1_1") (pintype "passive"))
      (node (ref "JP3") (pin "6") (pinfunction "6_6") (pintype "passive"))
      (node (ref "U$1") (pin "VBAT") (pinfunction "VBAT_VBAT") (pintype "bidirectional"))
    )
    (net (code "121") (name "/VDDA") (class "Default")
      (node (ref "C24") (pin "1") (pinfunction "1_1") (pintype "passive"))
      (node (ref "C25") (pin "+") (pinfunction "+_+") (pintype "passive"))
      (node (ref "L1") (pin "1") (pinfunction "1_1") (pintype "passive"))
      (node (ref "R1") (pin "2") (pinfunction "2_2") (pintype "passive"))
      (node (ref "U$1") (pin "VDDA") (pinfunction "VDD13_VDDA") (pintype "bidirectional"))
    )
    (net (code "122") (name "GND") (class "Default")
      (node (ref "C1") (pin "1") (pinfunction "1_1") (pintype "passive"))
      (node (ref "C10") (pin "1") (pinfunction "1_1") (pintype "passive"))
      (node (ref "C11") (pin "1") (pinfunction "1_1") (pintype "passive"))
      (node (ref "C12") (pin "1") (pinfunction "1_1") (pintype "passive"))
      (node (ref "C13") (pin "1") (pinfunction "1_1") (pintype "passive"))
      (node (ref "C14") (pin "-") (pinfunction "-_-") (pintype "passive"))
      (node (ref "C15") (pin "-") (pinfunction "-_-") (pintype "passive"))
      (node (ref "C16") (pin "-") (pinfunction "-_-") (pintype "passive"))
      (node (ref "C17") (pin "-") (pinfunction "-_-") (pintype "passive"))
      (node (ref "C18") (pin "2") (pinfunction "2_2") (pintype "passive"))
      (node (ref "C19") (pin "2") (pinfunction "2_2") (pintype "passive"))
      (node (ref "C2") (pin "1") (pinfunction "1_1") (pintype "passive"))
      (node (ref "C20") (pin "2") (pinfunction "2_2") (pintype "passive"))
      (node (ref "C21") (pin "2") (pinfunction "2_2") (pintype "passive"))
      (node (ref "C22") (pin "2") (pinfunction "2_2") (pintype "passive"))
      (node (ref "C23") (pin "1") (pinfunction "1_1") (pintype "passive"))
      (node (ref "C24") (pin "2") (pinfunction "2_2") (pintype "passive"))
      (node (ref "C25") (pin "-") (pinfunction "-_-") (pintype "passive"))
      (node (ref "C26") (pin "-") (pinfunction "-_-") (pintype "passive"))
      (node (ref "C27") (pin "1") (pinfunction "1_1") (pintype "passive"))
      (node (ref "C28") (pin "1") (pinfunction "1_1") (pintype "passive"))
      (node (ref "C29") (pin "1") (pinfunction "1_1") (pintype "passive"))
      (node (ref "C3") (pin "1") (pinfunction "1_1") (pintype "passive"))
      (node (ref "C30") (pin "1") (pinfunction "1_1") (pintype "passive"))
      (node (ref "C31") (pin "1") (pinfunction "1_1") (pintype "passive"))
      (node (ref "C32") (pin "1") (pinfunction "1_1") (pintype "passive"))
      (node (ref "C33") (pin "1") (pinfunction "1_1") (pintype "passive"))
      (node (ref "C34") (pin "2") (pinfunction "2_2") (pintype "passive"))
      (node (ref "C4") (pin "1") (pinfunction "1_1") (pintype "passive"))
      (node (ref "C5") (pin "1") (pinfunction "1_1") (pintype "passive"))
      (node (ref "C6") (pin "1") (pinfunction "1_1") (pintype "passive"))
      (node (ref "C7") (pin "1") (pinfunction "1_1") (pintype "passive"))
      (node (ref "C8") (pin "1") (pinfunction "1_1") (pintype "passive"))
      (node (ref "C9") (pin "1") (pinfunction "1_1") (pintype "passive"))
      (node (ref "IC1") (pin "1") (pinfunction "ADJ_1") (pintype "input"))
      (node (ref "IC2") (pin "1") (pinfunction "ADJ_1") (pintype "input"))
      (node (ref "IC3") (pin "18") (pinfunction "GND_18") (pintype "power_in"))
      (node (ref "IC3") (pin "21") (pinfunction "GND_21") (pintype "power_in"))
      (node (ref "IC3") (pin "25") (pinfunction "GND_25") (pintype "power_in"))
      (node (ref "IC3") (pin "26") (pinfunction "TEST_26") (pintype "input"))
      (node (ref "IC3") (pin "7") (pinfunction "GND_7") (pintype "power_in"))
      (node (ref "J1") (pin "1") (pinfunction "1_1") (pintype "passive"))
      (node (ref "J1") (pin "2") (pinfunction "2_2") (pintype "passive"))
      (node (ref "JP3") (pin "59") (pinfunction "59_59") (pintype "passive"))
      (node (ref "JP3") (pin "60") (pinfunction "60_60") (pintype "passive"))
      (node (ref "JP4") (pin "60") (pinfunction "60_60") (pintype "passive"))
      (node (ref "JP5") (pin "10") (pinfunction "10_10") (pintype "passive"))
      (node (ref "JP5") (pin "12") (pinfunction "12_12") (pintype "passive"))
      (node (ref "JP5") (pin "14") (pinfunction "14_14") (pintype "passive"))
      (node (ref "JP5") (pin "2") (pinfunction "2_2") (pintype "passive"))
      (node (ref "JP5") (pin "4") (pinfunction "4_4") (pintype "passive"))
      (node (ref "JP5") (pin "6") (pinfunction "6_6") (pintype "passive"))
      (node (ref "JP5") (pin "8") (pinfunction "8_8") (pintype "passive"))
      (node (ref "JP7") (pin "2") (pinfunction "2_2") (pintype "passive"))
      (node (ref "LED1") (pin "C") (pinfunction "C_C") (pintype "passive"))
      (node (ref "LED2") (pin "C") (pinfunction "C_C") (pintype "passive"))
      (node (ref "R8") (pin "2") (pinfunction "2_2") (pintype "passive"))
      (node (ref "S1") (pin "B2") (pinfunction "2_B2") (pintype "passive"))
      (node (ref "SJ1") (pin "2") (pinfunction "2_2") (pintype "passive"))
      (node (ref "SJ2") (pin "2") (pinfunction "2_2") (pintype "passive"))
      (node (ref "U$1") (pin "VSS") (pinfunction "VSS1_VSS") (pintype "bidirectional"))
      (node (ref "U$1") (pin "VSS2") (pinfunction "VSS2_VSS2") (pintype "bidirectional"))
      (node (ref "U$1") (pin "VSS3") (pinfunction "VSS3_VSS3") (pintype "bidirectional"))
      (node (ref "U$1") (pin "VSS4") (pinfunction "VSS4_VSS4") (pintype "bidirectional"))
      (node (ref "U$1") (pin "VSS5") (pinfunction "VSS5_VSS5") (pintype "bidirectional"))
      (node (ref "U$1") (pin "VSS6") (pinfunction "VSS6_VSS6") (pintype "bidirectional"))
      (node (ref "U$1") (pin "VSS7") (pinfunction "VSS7_VSS7") (pintype "bidirectional"))
      (node (ref "U$1") (pin "VSS8") (pinfunction "VSS8_VSS8") (pintype "bidirectional"))
      (node (ref "U$1") (pin "VSS9") (pinfunction "VSS9_VSS9") (pintype "bidirectional"))
      (node (ref "U$1") (pin "VSSA") (pinfunction "VSS10_VSSA") (pintype "bidirectional"))
      (node (ref "X1") (pin "5") (pinfunction "5_5") (pintype "passive"))
      (node (ref "X4") (pin "5") (pinfunction "5_5") (pintype "passive"))
    )
    (net (code "123") (name "Net-(C23-Pad2)") (class "Default")
      (node (ref "C23") (pin "2") (pinfunction "2_2") (pintype "passive"))
      (node (ref "C26") (pin "+") (pinfunction "+_+") (pintype "passive"))
      (node (ref "R1") (pin "1") (pinfunction "1_1") (pintype "passive"))
      (node (ref "U$1") (pin "VREF+") (pinfunction "VREF+_VREF+") (pintype "bidirectional"))
    )
    (net (code "124") (name "Net-(C27-Pad2)") (class "Default")
      (node (ref "C27") (pin "2") (pinfunction "2_2") (pintype "passive"))
      (node (ref "U$1") (pin "VCAP_1") (pinfunction "VCAP_1_VCAP_1") (pintype "bidirectional"))
    )
    (net (code "125") (name "Net-(C28-Pad2)") (class "Default")
      (node (ref "C28") (pin "2") (pinfunction "2_2") (pintype "passive"))
      (node (ref "U$1") (pin "VCAP_2") (pinfunction "VCAP_2_VCAP_2") (pintype "bidirectional"))
    )
    (net (code "126") (name "Net-(C29-Pad2)") (class "Default")
      (node (ref "C29") (pin "2") (pinfunction "2_2") (pintype "passive"))
      (node (ref "Q1") (pin "1") (pinfunction "1_1") (pintype "passive"))
      (node (ref "SJ6") (pin "2") (pinfunction "2_2") (pintype "passive"))
      (node (ref "U$1") (pin "PH1/OSC_OUT") (pinfunction "PH1/OSC_OUT_PH1/OSC_OUT") (pintype "bidirectional"))
    )
    (net (code "127") (name "Net-(C30-Pad2)") (class "Default")
      (node (ref "C30") (pin "2") (pinfunction "2_2") (pintype "passive"))
      (node (ref "Q1") (pin "2") (pinfunction "2_2") (pintype "passive"))
      (node (ref "SJ7") (pin "2") (pinfunction "2_2") (pintype "passive"))
      (node (ref "U$1") (pin "PH0/OSC_IN") (pinfunction "PH0/OSC_IN_PH0/OSC_IN") (pintype "bidirectional"))
    )
    (net (code "128") (name "Net-(C31-Pad2)") (class "Default")
      (node (ref "C31") (pin "2") (pinfunction "2_2") (pintype "passive"))
      (node (ref "Q2") (pin "1") (pinfunction "1_1") (pintype "passive"))
      (node (ref "SJ5") (pin "1") (pinfunction "1_1") (pintype "passive"))
    )
    (net (code "129") (name "Net-(D1-PadA)") (class "Default")
      (node (ref "D1") (pin "A") (pinfunction "A_A") (pintype "passive"))
      (node (ref "J1") (pin "3") (pinfunction "3_3") (pintype "passive"))
    )
    (net (code "130") (name "Net-(D1-PadC)") (class "Default")
      (node (ref "D1") (pin "C") (pinfunction "C_C") (pintype "passive"))
      (node (ref "JP1") (pin "4") (pinfunction "4_4") (pintype "passive"))
    )
    (net (code "131") (name "Net-(IC1-VI)") (class "Default")
      (node (ref "C16") (pin "+") (pinfunction "+_+") (pintype "passive"))
      (node (ref "C18") (pin "1") (pinfunction "1_1") (pintype "passive"))
      (node (ref "IC1") (pin "3") (pinfunction "VI_3") (pintype "input"))
      (node (ref "JP1") (pin "2") (pinfunction "2_2") (pintype "passive"))
      (node (ref "JP2") (pin "2") (pinfunction "2_2") (pintype "passive"))
    )
    (net (code "132") (name "Net-(IC3-3V3OUT)") (class "Default")
      (node (ref "C34") (pin "1") (pinfunction "1_1") (pintype "passive"))
      (node (ref "IC3") (pin "17") (pinfunction "3V3OUT_17") (pintype "output"))
    )
    (net (code "133") (name "Net-(IC3-CBUS0)") (class "Default")
      (node (ref "IC3") (pin "23") (pinfunction "CBUS0_23") (pintype "bidirectional"))
      (node (ref "R9") (pin "1") (pinfunction "1_1") (pintype "passive"))
    )
    (net (code "134") (name "Net-(IC3-CBUS1)") (class "Default")
      (node (ref "IC3") (pin "22") (pinfunction "CBUS1_22") (pintype "bidirectional"))
      (node (ref "R5") (pin "1") (pinfunction "1_1") (pintype "passive"))
    )
    (net (code "135") (name "Net-(IC3-RXD)") (class "Default")
      (node (ref "IC3") (pin "5") (pinfunction "RXD_5") (pintype "input"))
      (node (ref "SJ15") (pin "2") (pinfunction "2_2") (pintype "passive"))
    )
    (net (code "136") (name "Net-(IC3-TXD)") (class "Default")
      (node (ref "IC3") (pin "1") (pinfunction "TXD_1") (pintype "output"))
      (node (ref "SJ14") (pin "2") (pinfunction "2_2") (pintype "passive"))
    )
    (net (code "137") (name "Net-(IC3-USBDM)") (class "Default")
      (node (ref "IC3") (pin "16") (pinfunction "USBDM_16") (pintype "bidirectional"))
      (node (ref "X4") (pin "2") (pinfunction "2_2") (pintype "passive"))
    )
    (net (code "138") (name "Net-(IC3-USBDP)") (class "Default")
      (node (ref "IC3") (pin "15") (pinfunction "USBDP_15") (pintype "bidirectional"))
      (node (ref "X4") (pin "3") (pinfunction "3_3") (pintype "passive"))
    )
    (net (code "139") (name "Net-(IC3-~{CTS})") (class "Default")
      (node (ref "IC3") (pin "11") (pinfunction "~{CTS}_11") (pintype "input"))
      (node (ref "IC3") (pin "3") (pinfunction "~{RTS}_3") (pintype "output"))
    )
    (net (code "140") (name "Net-(IC3-~{RESET})") (class "Default")
      (node (ref "IC3") (pin "19") (pinfunction "~{RESET}_19") (pintype "input"))
      (node (ref "R6") (pin "2") (pinfunction "2_2") (pintype "passive"))
    )
    (net (code "141") (name "Net-(JP1-Pad1)") (class "Default")
      (node (ref "JP1") (pin "1") (pinfunction "1_1") (pintype "passive"))
      (node (ref "X1") (pin "1") (pinfunction "1_1") (pintype "passive"))
    )
    (net (code "142") (name "Net-(LED1-PadA)") (class "Default")
      (node (ref "LED1") (pin "A") (pinfunction "A_A") (pintype "passive"))
      (node (ref "R3") (pin "2") (pinfunction "2_2") (pintype "passive"))
    )
    (net (code "143") (name "Net-(LED2-PadA)") (class "Default")
      (node (ref "LED2") (pin "A") (pinfunction "A_A") (pintype "passive"))
      (node (ref "R4") (pin "2") (pinfunction "2_2") (pintype "passive"))
    )
    (net (code "144") (name "Net-(LED3-PadC)") (class "Default")
      (node (ref "LED3") (pin "C") (pinfunction "C_C") (pintype "passive"))
      (node (ref "R9") (pin "2") (pinfunction "2_2") (pintype "passive"))
    )
    (net (code "145") (name "Net-(LED4-PadC)") (class "Default")
      (node (ref "LED4") (pin "C") (pinfunction "C_C") (pintype "passive"))
      (node (ref "R5") (pin "2") (pinfunction "2_2") (pintype "passive"))
    )
    (net (code "146") (name "Net-(Q2-2)") (class "Default")
      (node (ref "C32") (pin "2") (pinfunction "2_2") (pintype "passive"))
      (node (ref "Q2") (pin "4") (pinfunction "2_4") (pintype "passive"))
      (node (ref "SJ4") (pin "1") (pinfunction "1_1") (pintype "passive"))
    )
    (net (code "147") (name "Net-(R2-Pad1)") (class "Default")
      (node (ref "R2") (pin "1") (pinfunction "1_1") (pintype "passive"))
      (node (ref "SJ1") (pin "1") (pinfunction "1_1") (pintype "passive"))
    )
    (net (code "148") (name "Net-(R8-Pad1)") (class "Default")
      (node (ref "R8") (pin "1") (pinfunction "1_1") (pintype "passive"))
      (node (ref "X1") (pin "4") (pinfunction "4_4") (pintype "passive"))
    )
    (net (code "149") (name "Net-(SJ2-Pad1)") (class "Default")
      (node (ref "SJ2") (pin "1") (pinfunction "1_1") (pintype "passive"))
      (node (ref "SJ3") (pin "1") (pinfunction "1_1") (pintype "passive"))
      (node (ref "U$1") (pin "PDR_ON") (pinfunction "PDR_ON_PDR_ON") (pintype "bidirectional"))
    )
    (net (code "150") (name "unconnected-(IC3-CBUS2-Pad13)") (class "Default")
      (node (ref "IC3") (pin "13") (pinfunction "CBUS2_13") (pintype "bidirectional"))
    )
    (net (code "151") (name "unconnected-(IC3-CBUS3-Pad14)") (class "Default")
      (node (ref "IC3") (pin "14") (pinfunction "CBUS3_14") (pintype "bidirectional"))
    )
    (net (code "152") (name "unconnected-(IC3-CBUS4-Pad12)") (class "Default")
      (node (ref "IC3") (pin "12") (pinfunction "CBUS4_12") (pintype "bidirectional"))
    )
    (net (code "153") (name "unconnected-(IC3-OSCI-Pad27)") (class "Default")
      (node (ref "IC3") (pin "27") (pinfunction "OSCI_27") (pintype "input"))
    )
    (net (code "154") (name "unconnected-(IC3-OSCO-Pad28)") (class "Default")
      (node (ref "IC3") (pin "28") (pinfunction "OSCO_28") (pintype "output"))
    )
    (net (code "155") (name "unconnected-(IC3-~{DCD}-Pad10)") (class "Default")
      (node (ref "IC3") (pin "10") (pinfunction "~{DCD}_10") (pintype "input"))
    )
    (net (code "156") (name "unconnected-(IC3-~{DSR}-Pad9)") (class "Default")
      (node (ref "IC3") (pin "9") (pinfunction "~{DSR}_9") (pintype "input"))
    )
    (net (code "157") (name "unconnected-(IC3-~{DTR}-Pad2)") (class "Default")
      (node (ref "IC3") (pin "2") (pinfunction "~{DTR}_2") (pintype "output"))
    )
    (net (code "158") (name "unconnected-(IC3-~{RI}-Pad6)") (class "Default")
      (node (ref "IC3") (pin "6") (pinfunction "~{RI}_6") (pintype "input"))
    )
    (net (code "159") (name "unconnected-(X1-Pad2)") (class "Default")
      (node (ref "X1") (pin "2") (pinfunction "2_2") (pintype "passive"))
    )
    (net (code "160") (name "unconnected-(X1-Pad3)") (class "Default")
      (node (ref "X1") (pin "3") (pinfunction "3_3") (pintype "passive"))
    )
    (net (code "161") (name "unconnected-(X4-Pad1)") (class "Default")
      (node (ref "X4") (pin "1") (pinfunction "1_1") (pintype "passive"))
    )
    (net (code "162") (name "unconnected-(X4-Pad4)") (class "Default")
      (node (ref "X4") (pin "4") (pinfunction "4_4") (pintype "passive"))
    )
  )
)
